# CELL_PHONE_DETECTOR.net
KiCad netlist of a schematic drawn in EAGLE
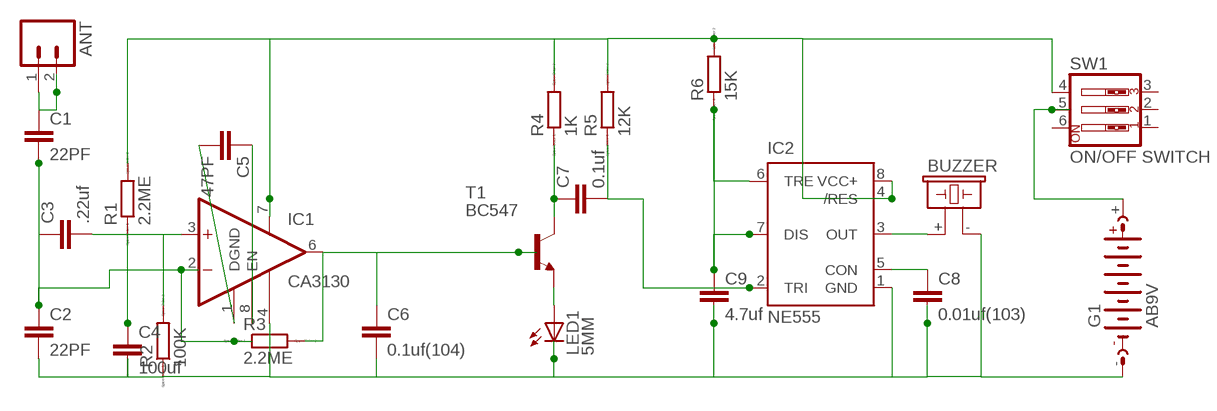
[diagram p0: schematic, sheet 1]

(export (version "E")
  (design (tool "Eeschema 10.0.6"))
  (components
    (comp (ref "ANT")
      (value "M02")
      (footprint "eagle-import:02P")
      (libsource (lib "eagle-import") (part "M02"))
    )
    (comp (ref "BUZZER")
      (value "F/CM12P")
      (footprint "eagle-import:F_CM12P")
      (libsource (lib "eagle-import") (part "F/CM12P"))
    )
    (comp (ref "C1")
      (value "22PF")
      (footprint "eagle-import:C2.5-6")
      (libsource (lib "eagle-import") (part "C2.5/6"))
    )
    (comp (ref "C2")
      (value "22PF")
      (footprint "eagle-import:C2.5-6")
      (libsource (lib "eagle-import") (part "C2.5/6"))
    )
    (comp (ref "C3")
      (value ".22uf")
      (footprint "eagle-import:C5B7.2")
      (libsource (lib "eagle-import") (part "C5/7.2"))
    )
    (comp (ref "C4")
      (value "100uf")
      (footprint "eagle-import:C2.5-6")
      (libsource (lib "eagle-import") (part "C2.5/6"))
    )
    (comp (ref "C5")
      (value "47PF")
      (footprint "eagle-import:C5B5")
      (libsource (lib "eagle-import") (part "C5/5"))
    )
    (comp (ref "C6")
      (value "0.1uf(104)")
      (footprint "eagle-import:C5B5")
      (libsource (lib "eagle-import") (part "C5/5"))
    )
    (comp (ref "C7")
      (value "0.1uf")
      (footprint "eagle-import:C5B5")
      (libsource (lib "eagle-import") (part "C5/5"))
    )
    (comp (ref "C8")
      (value "0.01uf(103)")
      (footprint "eagle-import:C5B5")
      (libsource (lib "eagle-import") (part "C5/5"))
    )
    (comp (ref "C9")
      (value "4.7uf")
      (footprint "eagle-import:C2.5-3")
      (libsource (lib "eagle-import") (part "C2,5-3"))
    )
    (comp (ref "G1")
      (value "AB9V")
      (footprint "eagle-import:AB9V")
      (libsource (lib "eagle-import") (part "AB9V"))
    )
    (comp (ref "IC1")
      (value "CA3130")
      (footprint "eagle-import:DIL08")
      (libsource (lib "eagle-import") (part "OPA726P"))
    )
    (comp (ref "IC2")
      (value "NE555")
      (footprint "eagle-import:DIL-08")
      (fields (field (name "MF") "Arrow Electronics") (field (name "MPN") "NE555N"))
      (libsource (lib "eagle-import") (part "NE555"))
    )
    (comp (ref "LED1")
      (value "5MM")
      (footprint "eagle-import:LED5MM")
      (libsource (lib "eagle-import") (part "LED5MM"))
    )
    (comp (ref "R1")
      (value "2.2ME")
      (footprint "eagle-import:0204_7")
      (libsource (lib "eagle-import") (part "R0204/7"))
    )
    (comp (ref "R2")
      (value "100K")
      (footprint "eagle-import:0204_7")
      (libsource (lib "eagle-import") (part "R0204/7"))
    )
    (comp (ref "R3")
      (value "2.2ME")
      (footprint "eagle-import:0204_7")
      (libsource (lib "eagle-import") (part "R0204/7"))
    )
    (comp (ref "R4")
      (value "1K")
      (footprint "eagle-import:0204_7")
      (libsource (lib "eagle-import") (part "R0204/7"))
    )
    (comp (ref "R5")
      (value "12K")
      (footprint "eagle-import:0204_7")
      (libsource (lib "eagle-import") (part "R0204/7"))
    )
    (comp (ref "R6")
      (value "15K")
      (footprint "eagle-import:0204_7")
      (libsource (lib "eagle-import") (part "R0204/7"))
    )
    (comp (ref "SW1")
      (value "ON/OFF SWITCH")
      (footprint "eagle-import:EDG-03")
      (libsource (lib "eagle-import") (part "SW_DIP-3"))
    )
    (comp (ref "T1")
      (value "BC547")
      (footprint "eagle-import:TO92")
      (libsource (lib "eagle-import") (part "BC547"))
    )
  )
  (nets
    (net (code "1") (name "Net-(ANT-Pad1)") (class "Default")
      (node (ref "ANT") (pin "1") (pinfunction "1_1") (pintype "passive"))
      (node (ref "ANT") (pin "2") (pinfunction "2_2") (pintype "passive"))
      (node (ref "C1") (pin "1") (pinfunction "1_1") (pintype "passive"))
    )
    (net (code "2") (name "Net-(BUZZER-1)") (class "Default")
      (node (ref "BUZZER") (pin "+") (pinfunction "1_+") (pintype "passive"))
      (node (ref "IC2") (pin "3") (pinfunction "OUT_3") (pintype "output"))
    )
    (net (code "3") (name "Net-(BUZZER-2)") (class "Default")
      (node (ref "BUZZER") (pin "-") (pinfunction "2_-") (pintype "passive"))
      (node (ref "C2") (pin "2") (pinfunction "2_2") (pintype "passive"))
      (node (ref "C4") (pin "2") (pinfunction "2_2") (pintype "passive"))
      (node (ref "C6") (pin "2") (pinfunction "2_2") (pintype "passive"))
      (node (ref "C8") (pin "2") (pinfunction "2_2") (pintype "passive"))
      (node (ref "C9") (pin "2") (pinfunction "2_2") (pintype "passive"))
      (node (ref "G1") (pin "-") (pinfunction "-_-") (pintype "passive"))
      (node (ref "IC1") (pin "4") (pinfunction "V-_4") (pintype "power_in"))
      (node (ref "IC2") (pin "1") (pinfunction "GND_1") (pintype "power_in"))
      (node (ref "LED1") (pin "K") (pinfunction "C_K") (pintype "passive"))
      (node (ref "R2") (pin "1") (pinfunction "1_1") (pintype "passive"))
    )
    (net (code "4") (name "Net-(G1-Pad+)") (class "Default")
      (node (ref "G1") (pin "+") (pinfunction "+_+") (pintype "passive"))
      (node (ref "SW1") (pin "5") (pinfunction "5_5") (pintype "passive"))
    )
    (net (code "5") (name "Net-(IC1-+IN)") (class "Default")
      (node (ref "C3") (pin "2") (pinfunction "2_2") (pintype "passive"))
      (node (ref "C4") (pin "1") (pinfunction "1_1") (pintype "passive"))
      (node (ref "IC1") (pin "3") (pinfunction "+IN_3") (pintype "input"))
      (node (ref "R1") (pin "1") (pinfunction "1_1") (pintype "passive"))
      (node (ref "R2") (pin "2") (pinfunction "2_2") (pintype "passive"))
    )
    (net (code "6") (name "Net-(IC1--IN)") (class "Default")
      (node (ref "C1") (pin "2") (pinfunction "2_2") (pintype "passive"))
      (node (ref "C2") (pin "1") (pinfunction "1_1") (pintype "passive"))
      (node (ref "C3") (pin "1") (pinfunction "1_1") (pintype "passive"))
      (node (ref "IC1") (pin "2") (pinfunction "-IN_2") (pintype "input"))
      (node (ref "R3") (pin "1") (pinfunction "1_1") (pintype "passive"))
    )
    (net (code "7") (name "Net-(IC1-DGND)") (class "Default")
      (node (ref "C5") (pin "2") (pinfunction "2_2") (pintype "passive"))
      (node (ref "IC1") (pin "1") (pinfunction "DGND_1") (pintype "input"))
    )
    (net (code "8") (name "Net-(IC1-EN)") (class "Default")
      (node (ref "C5") (pin "1") (pinfunction "1_1") (pintype "passive"))
      (node (ref "IC1") (pin "8") (pinfunction "EN_8") (pintype "input"))
    )
    (net (code "9") (name "Net-(IC1-OUT)") (class "Default")
      (node (ref "C6") (pin "1") (pinfunction "1_1") (pintype "passive"))
      (node (ref "IC1") (pin "6") (pinfunction "OUT_6") (pintype "output"))
      (node (ref "R3") (pin "2") (pinfunction "2_2") (pintype "passive"))
      (node (ref "T1") (pin "2") (pinfunction "B_2") (pintype "passive"))
    )
    (net (code "10") (name "Net-(IC1-V+)") (class "Default")
      (node (ref "IC1") (pin "7") (pinfunction "V+_7") (pintype "power_in"))
      (node (ref "IC2") (pin "4") (pinfunction "/RES_4") (pintype "input"))
      (node (ref "IC2") (pin "8") (pinfunction "VCC+_8") (pintype "power_in"))
      (node (ref "R1") (pin "2") (pinfunction "2_2") (pintype "passive"))
      (node (ref "R4") (pin "2") (pinfunction "2_2") (pintype "passive"))
      (node (ref "R5") (pin "2") (pinfunction "2_2") (pintype "passive"))
      (node (ref "R6") (pin "2") (pinfunction "2_2") (pintype "passive"))
      (node (ref "SW1") (pin "4") (pinfunction "4_4") (pintype "passive"))
    )
    (net (code "11") (name "Net-(IC2-CON)") (class "Default")
      (node (ref "C8") (pin "1") (pinfunction "1_1") (pintype "passive"))
      (node (ref "IC2") (pin "5") (pinfunction "CON_5") (pintype "input"))
    )
    (net (code "12") (name "Net-(IC2-DIS)") (class "Default")
      (node (ref "C9") (pin "1") (pinfunction "1_1") (pintype "passive"))
      (node (ref "IC2") (pin "6") (pinfunction "TRE_6") (pintype "input"))
      (node (ref "IC2") (pin "7") (pinfunction "DIS_7") (pintype "input"))
      (node (ref "R6") (pin "1") (pinfunction "1_1") (pintype "passive"))
    )
    (net (code "13") (name "Net-(IC2-TRI)") (class "Default")
      (node (ref "C7") (pin "2") (pinfunction "2_2") (pintype "passive"))
      (node (ref "IC2") (pin "2") (pinfunction "TRI_2") (pintype "input"))
      (node (ref "R5") (pin "1") (pinfunction "1_1") (pintype "passive"))
    )
    (net (code "14") (name "Net-(T1-C)") (class "Default")
      (node (ref "C7") (pin "1") (pinfunction "1_1") (pintype "passive"))
      (node (ref "R4") (pin "1") (pinfunction "1_1") (pintype "passive"))
      (node (ref "T1") (pin "3") (pinfunction "C_3") (pintype "passive"))
    )
    (net (code "15") (name "Net-(T1-E)") (class "Default")
      (node (ref "LED1") (pin "A") (pinfunction "A_A") (pintype "passive"))
      (node (ref "T1") (pin "1") (pinfunction "E_1") (pintype "passive"))
    )
    (net (code "16") (name "unconnected-(SW1-Pad1)") (class "Default")
      (node (ref "SW1") (pin "1") (pinfunction "1_1") (pintype "passive"))
    )
    (net (code "17") (name "unconnected-(SW1-Pad2)") (class "Default")
      (node (ref "SW1") (pin "2") (pinfunction "2_2") (pintype "passive"))
    )
    (net (code "18") (name "unconnected-(SW1-Pad3)") (class "Default")
      (node (ref "SW1") (pin "3") (pinfunction "3_3") (pintype "passive"))
    )
    (net (code "19") (name "unconnected-(SW1-Pad6)") (class "Default")
      (node (ref "SW1") (pin "6") (pinfunction "6_6") (pintype "passive"))
    )
  )
)
